# SENSORVALVULAF.net
KiCad netlist of a schematic drawn in EAGLE
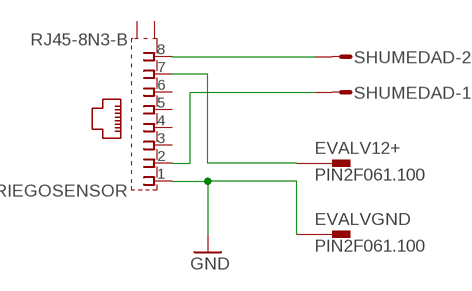
[diagram p0: schematic, sheet 1]

(export (version "E")
  (design (tool "Eeschema 10.0.6"))
  (components
    (comp (ref "EVALV12+")
      (value "PIN2F061.100")
      (footprint "eagle-import:F061.100")
      (libsource (lib "eagle-import") (part "PIN2F061.100"))
    )
    (comp (ref "EVALVGND")
      (value "PIN2F061.100")
      (footprint "eagle-import:F061.100")
      (libsource (lib "eagle-import") (part "PIN2F061.100"))
    )
    (comp (ref "RIEGOSENSOR")
      (value "RJ45-8N3-B")
      (footprint "eagle-import:TE_RJ45-8N3-B")
      (fields (field (name "COMMENT") "1-6609212-3") (field (name "MF") "TE Connectivity"))
      (libsource (lib "eagle-import") (part "RJ45-8N3-B"))
    )
    (comp (ref "SHUMEDAD")
      (value "L02P")
      (footprint "eagle-import:L02P")
      (libsource (lib "eagle-import") (part "L02P"))
    )
  )
  (nets
    (net (code "1") (name "GND") (class "Default")
      (node (ref "EVALVGND") (pin "A1") (pinfunction "1_A1") (pintype "passive"))
      (node (ref "EVALVGND") (pin "A2") (pinfunction "1_A2") (pintype "passive"))
      (node (ref "RIEGOSENSOR") (pin "1") (pinfunction "1_1") (pintype "passive"))
    )
    (net (code "2") (name "Net-(EVALV12+-1-PadA1)") (class "Default")
      (node (ref "EVALV12+") (pin "A1") (pinfunction "1_A1") (pintype "passive"))
      (node (ref "EVALV12+") (pin "A2") (pinfunction "1_A2") (pintype "passive"))
      (node (ref "RIEGOSENSOR") (pin "7") (pinfunction "7_7") (pintype "passive"))
    )
    (net (code "3") (name "Net-(SHUMEDADA-S)") (class "Default")
      (node (ref "RIEGOSENSOR") (pin "2") (pinfunction "2_2") (pintype "passive"))
      (node (ref "SHUMEDAD") (pin "1") (pinfunction "S_1") (pintype "passive"))
    )
    (net (code "4") (name "Net-(SHUMEDADB-S)") (class "Default")
      (node (ref "RIEGOSENSOR") (pin "8") (pinfunction "8_8") (pintype "passive"))
      (node (ref "SHUMEDAD") (pin "2") (pinfunction "S_2") (pintype "passive"))
    )
    (net (code "5") (name "unconnected-(RIEGOSENSOR-Pad3)") (class "Default")
      (node (ref "RIEGOSENSOR") (pin "3") (pinfunction "3_3") (pintype "passive"))
    )
    (net (code "6") (name "unconnected-(RIEGOSENSOR-Pad4)") (class "Default")
      (node (ref "RIEGOSENSOR") (pin "4") (pinfunction "4_4") (pintype "passive"))
    )
    (net (code "7") (name "unconnected-(RIEGOSENSOR-Pad5)") (class "Default")
      (node (ref "RIEGOSENSOR") (pin "5") (pinfunction "5_5") (pintype "passive"))
    )
    (net (code "8") (name "unconnected-(RIEGOSENSOR-Pad6)") (class "Default")
      (node (ref "RIEGOSENSOR") (pin "6") (pinfunction "6_6") (pintype "passive"))
    )
    (net (code "9") (name "unconnected-(RIEGOSENSOR-S1-Pad9)") (class "Default")
      (node (ref "RIEGOSENSOR") (pin "9") (pinfunction "S1_9") (pintype "passive"))
    )
    (net (code "10") (name "unconnected-(RIEGOSENSOR-S2-Pad10)") (class "Default")
      (node (ref "RIEGOSENSOR") (pin "10") (pinfunction "S2_10") (pintype "passive"))
    )
  )
)
